# Schaltplan_VoltageLevelShifter.net
KiCad netlist of a schematic drawn in EAGLE
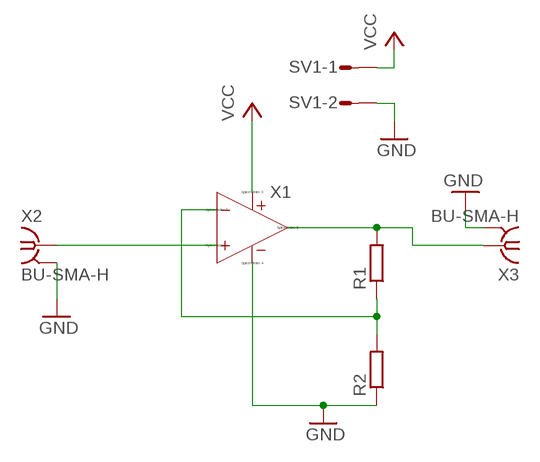
[diagram p0: schematic, sheet 1]

(export (version "E")
  (design (tool "Eeschema 10.0.6"))
  (components
    (comp (ref "R1")
      (value "R-EU_0204/7")
      (footprint "eagle-import:0204_7")
      (libsource (lib "eagle-import") (part "R-EU_0204/7"))
    )
    (comp (ref "R2")
      (value "R-EU_0204/7")
      (footprint "eagle-import:0204_7")
      (libsource (lib "eagle-import") (part "R-EU_0204/7"))
    )
    (comp (ref "SV1")
      (value "S02P")
      (footprint "eagle-import:S02P")
      (libsource (lib "eagle-import") (part "S02P"))
    )
    (comp (ref "X1")
      (value "UNIVERSALOPAMP2")
      (footprint "eagle-import:S8")
      (libsource (lib "eagle-import") (part "UNIVERSALOPAMP2"))
    )
    (comp (ref "X2")
      (value "BU-SMA-H")
      (footprint "eagle-import:BU-SMA-H")
      (libsource (lib "eagle-import") (part "BU-SMA-H"))
    )
    (comp (ref "X3")
      (value "BU-SMA-H")
      (footprint "eagle-import:BU-SMA-H")
      (libsource (lib "eagle-import") (part "BU-SMA-H"))
    )
  )
  (nets
    (net (code "1") (name "GND") (class "Default")
      (node (ref "R2") (pin "1") (pinfunction "1_1") (pintype "passive"))
      (node (ref "SV1") (pin "2") (pinfunction "S_2") (pintype "passive"))
      (node (ref "X1") (pin "4") (pinfunction "V-_4") (pintype "passive"))
      (node (ref "X2") (pin "2") (pinfunction "2_2") (pintype "passive"))
      (node (ref "X2") (pin "3") (pinfunction "2_3") (pintype "passive"))
      (node (ref "X2") (pin "4") (pinfunction "2_4") (pintype "passive"))
      (node (ref "X2") (pin "5") (pinfunction "2_5") (pintype "passive"))
      (node (ref "X3") (pin "2") (pinfunction "2_2") (pintype "passive"))
      (node (ref "X3") (pin "3") (pinfunction "2_3") (pintype "passive"))
      (node (ref "X3") (pin "4") (pinfunction "2_4") (pintype "passive"))
      (node (ref "X3") (pin "5") (pinfunction "2_5") (pintype "passive"))
    )
    (net (code "2") (name "Net-(X1-IN+)") (class "Default")
      (node (ref "X1") (pin "1") (pinfunction "IN+_1") (pintype "passive"))
      (node (ref "X2") (pin "1") (pinfunction "1_1") (pintype "passive"))
    )
    (net (code "3") (name "Net-(X1-IN-)") (class "Default")
      (node (ref "R1") (pin "1") (pinfunction "1_1") (pintype "passive"))
      (node (ref "R2") (pin "2") (pinfunction "2_2") (pintype "passive"))
      (node (ref "X1") (pin "2") (pinfunction "IN-_2") (pintype "passive"))
    )
    (net (code "4") (name "Net-(X1-OUT)") (class "Default")
      (node (ref "R1") (pin "2") (pinfunction "2_2") (pintype "passive"))
      (node (ref "X1") (pin "3") (pinfunction "OUT_3") (pintype "passive"))
      (node (ref "X3") (pin "1") (pinfunction "1_1") (pintype "passive"))
    )
    (net (code "5") (name "VCC") (class "Default")
      (node (ref "SV1") (pin "1") (pinfunction "S_1") (pintype "passive"))
      (node (ref "X1") (pin "8") (pinfunction "V+_8") (pintype "passive"))
    )
  )
)
